# I2C_Peripherals.net
KiCad netlist of a schematic drawn in Altium Designer
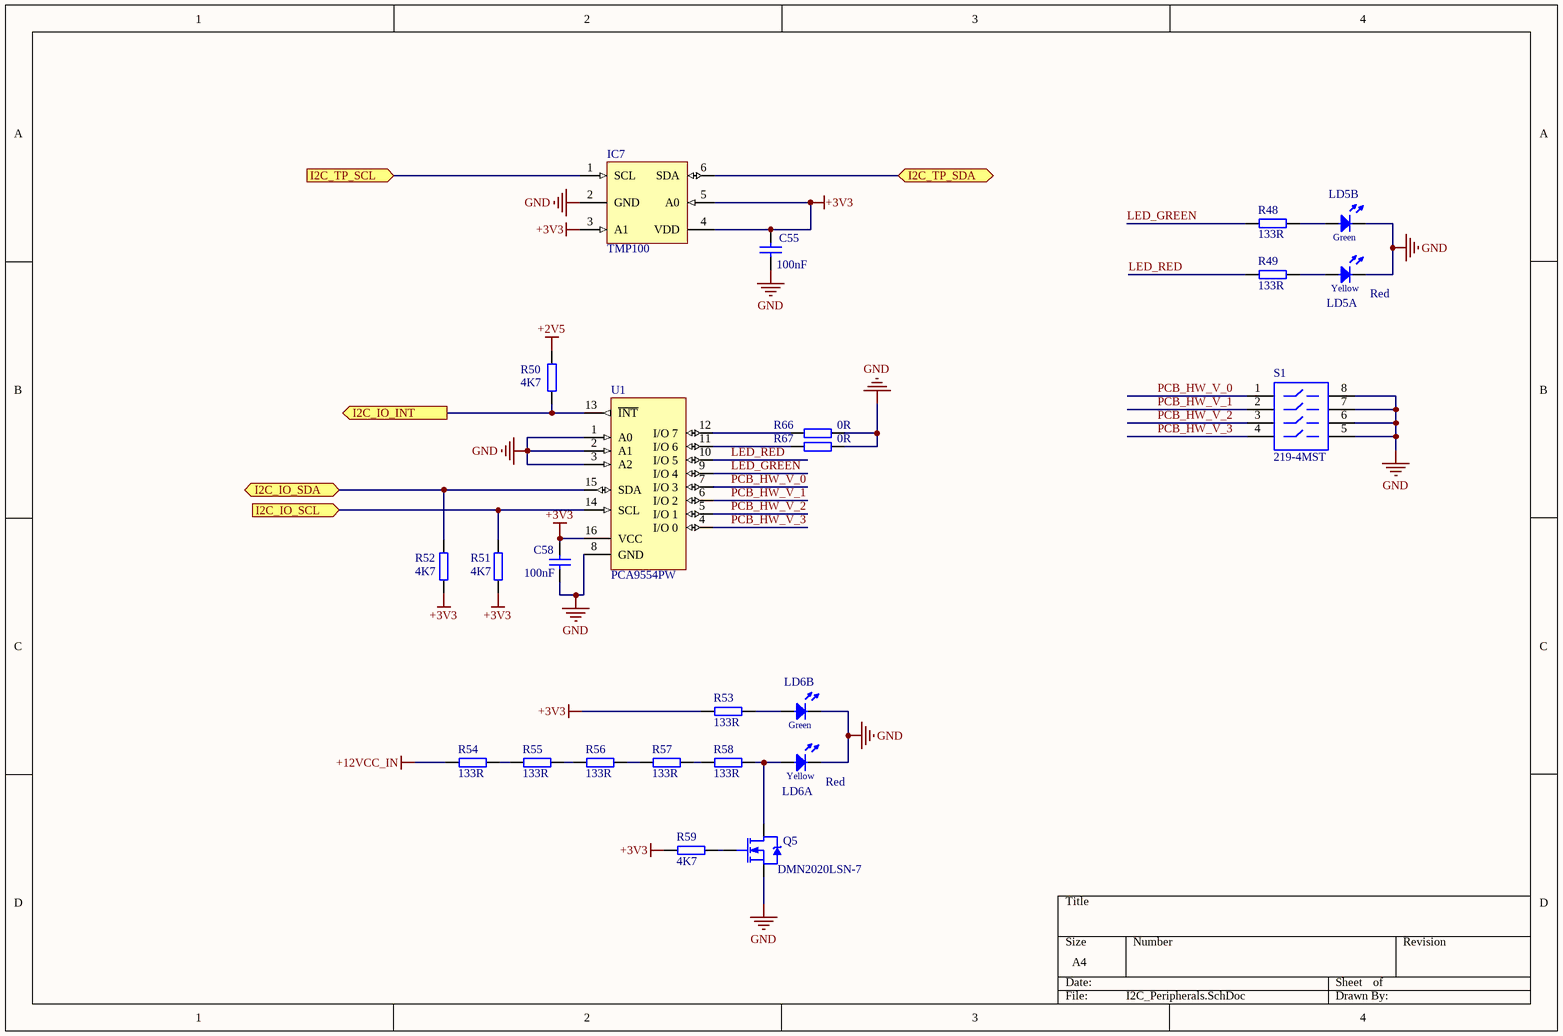
[diagram p0: I2C_Peripherals.SchDoc]

(export (version "E")
  (design (tool "Eeschema 10.0.6"))
  (components
    (comp (ref "C55")
      (value "100nF")
      (footprint "CC1608-0603")
      (description "Capacitor")
      (fields
        (field (name "TOLERANCE") "±10%")
        (field (name "VOLTAGE") "16V")
        (field (name "PUBLISHER") "Altium Limited")
      )
      (libsource (lib "wr_switch") (part "Cap"))
    )
    (comp (ref "C58")
      (value "100nF")
      (footprint "CC1608-0603")
      (description "Capacitor")
      (fields
        (field (name "TOLERANCE") "±10%")
        (field (name "VOLTAGE") "16V")
        (field (name "PUBLISHER") "Altium Limited")
      )
      (libsource (lib "wr_switch") (part "Cap"))
    )
    (comp (ref "IC7")
      (value "TMP100")
      (footprint "SOT23A-6L")
      (description "I2C temp. sensor")
      (libsource (lib "wr_switch") (part "TMP100"))
    )
    (comp (ref "LD5")
      (value "Red")
      (footprint "7S_WR:LED_DIALIGHT_591-3x0x-0xx")
      (description "Bi-Color LED SMD")
      (libsource (lib "wr_switch") (part "LED_DIALIGHT_591-3x0x"))
    )
    (comp (ref "LD6")
      (value "Red")
      (footprint "7S_WR:LED_DIALIGHT_591-3x0x-0xx")
      (description "Bi-Color LED SMD")
      (libsource (lib "wr_switch") (part "LED_DIALIGHT_591-3x0x"))
    )
    (comp (ref "Q5")
      (value "DMN2020LSN-7")
      (footprint "7S_WR:SC-59-3")
      (description "N-Channel Power MOSFET")
      (fields (field (name "MANUFACTURER") "Diodes Inc.") (field (name "PUBLISHER") "Altium Limited"))
      (libsource (lib "wr_switch") (part "NMOS-2"))
    )
    (comp (ref "R48")
      (value "133R")
      (footprint "0603")
      (description "SMD Resistor")
      (fields (field (name "TOLERANCE") "±1%"))
      (libsource (lib "wr_switch") (part "RES_SMD"))
    )
    (comp (ref "R49")
      (value "133R")
      (footprint "0603")
      (description "SMD Resistor")
      (fields (field (name "TOLERANCE") "±1%"))
      (libsource (lib "wr_switch") (part "RES_SMD"))
    )
    (comp (ref "R50")
      (value "4K7")
      (footprint "0603")
      (description "SMD Resistor")
      (fields (field (name "TOLERANCE") "±1%"))
      (libsource (lib "wr_switch") (part "RES_SMD"))
    )
    (comp (ref "R51")
      (value "4K7")
      (footprint "0603")
      (description "SMD Resistor")
      (fields (field (name "TOLERANCE") "±1%"))
      (libsource (lib "wr_switch") (part "RES_SMD"))
    )
    (comp (ref "R52")
      (value "4K7")
      (footprint "0603")
      (description "SMD Resistor")
      (fields (field (name "TOLERANCE") "±1%"))
      (libsource (lib "wr_switch") (part "RES_SMD"))
    )
    (comp (ref "R53")
      (value "133R")
      (footprint "0603")
      (description "SMD Resistor")
      (fields (field (name "TOLERANCE") "±1%"))
      (libsource (lib "wr_switch") (part "RES_SMD"))
    )
    (comp (ref "R54")
      (value "133R")
      (footprint "0603")
      (description "SMD Resistor")
      (fields (field (name "TOLERANCE") "±1%"))
      (libsource (lib "wr_switch") (part "RES_SMD"))
    )
    (comp (ref "R55")
      (value "133R")
      (footprint "0603")
      (description "SMD Resistor")
      (fields (field (name "TOLERANCE") "±1%"))
      (libsource (lib "wr_switch") (part "RES_SMD"))
    )
    (comp (ref "R56")
      (value "133R")
      (footprint "0603")
      (description "SMD Resistor")
      (fields (field (name "TOLERANCE") "±1%"))
      (libsource (lib "wr_switch") (part "RES_SMD"))
    )
    (comp (ref "R57")
      (value "133R")
      (footprint "0603")
      (description "SMD Resistor")
      (fields (field (name "TOLERANCE") "±1%"))
      (libsource (lib "wr_switch") (part "RES_SMD"))
    )
    (comp (ref "R58")
      (value "133R")
      (footprint "0603")
      (description "SMD Resistor")
      (fields (field (name "TOLERANCE") "±1%"))
      (libsource (lib "wr_switch") (part "RES_SMD"))
    )
    (comp (ref "R59")
      (value "4K7")
      (footprint "0603")
      (description "SMD Resistor")
      (fields (field (name "TOLERANCE") "±1%"))
      (libsource (lib "wr_switch") (part "RES_SMD"))
    )
    (comp (ref "R66")
      (value "0R")
      (footprint "0603")
      (description "SMD Resistor")
      (libsource (lib "wr_switch") (part "RES_SMD"))
    )
    (comp (ref "R67")
      (value "0R")
      (footprint "0603")
      (description "SMD Resistor")
      (libsource (lib "wr_switch") (part "RES_SMD"))
    )
    (comp (ref "S1")
      (value "219-4MST")
      (footprint "NHDS-8")
      (description "4 Positions DIP SWITCH")
      (libsource (lib "wr_switch") (part "SW-DIP4"))
    )
    (comp (ref "U1")
      (value "PCA9554PW")
      (footprint "SOP65P640X120-16N")
      (description "8-bit I2C-bus SMBus I/O port with interrupt")
      (libsource (lib "wr_switch") (part "PCA9554D"))
    )
  )
  (nets
    (net (code "1") (name "+2V5") (class "Default")
      (node (ref "R50") (pin "2") (pinfunction "2_2") (pintype "passive"))
    )
    (net (code "2") (name "+3V3") (class "Default")
      (node (ref "C55") (pin "2") (pinfunction "2_2") (pintype "passive"))
      (node (ref "C58") (pin "1") (pinfunction "1_1") (pintype "passive"))
      (node (ref "IC7") (pin "3") (pinfunction "A1_3") (pintype "input"))
      (node (ref "IC7") (pin "4") (pinfunction "VDD_4") (pintype "power_in"))
      (node (ref "IC7") (pin "5") (pinfunction "A0_5") (pintype "input"))
      (node (ref "R51") (pin "2") (pinfunction "2_2") (pintype "passive"))
      (node (ref "R52") (pin "2") (pinfunction "2_2") (pintype "passive"))
      (node (ref "R53") (pin "1") (pinfunction "1_1") (pintype "passive"))
      (node (ref "R59") (pin "2") (pinfunction "2_2") (pintype "passive"))
      (node (ref "U1") (pin "16") (pinfunction "VCC_16") (pintype "power_in"))
    )
    (net (code "3") (name "+12VCC_IN") (class "Default")
      (node (ref "R54") (pin "1") (pinfunction "1_1") (pintype "passive"))
    )
    (net (code "4") (name "/I2C_IO_INT") (class "Default")
      (node (ref "R50") (pin "1") (pinfunction "1_1") (pintype "passive"))
      (node (ref "U1") (pin "13") (pinfunction "~{INT}_13") (pintype "output"))
    )
    (net (code "5") (name "/I2C_IO_SCL") (class "Default")
      (node (ref "R51") (pin "1") (pinfunction "1_1") (pintype "passive"))
      (node (ref "U1") (pin "14") (pinfunction "SCL_14") (pintype "input"))
    )
    (net (code "6") (name "/I2C_IO_SDA") (class "Default")
      (node (ref "R52") (pin "1") (pinfunction "1_1") (pintype "passive"))
      (node (ref "U1") (pin "15") (pinfunction "SDA_15") (pintype "bidirectional"))
    )
    (net (code "7") (name "/I2C_TP_SCL") (class "Default")
      (node (ref "IC7") (pin "1") (pinfunction "SCL_1") (pintype "input"))
    )
    (net (code "8") (name "/I2C_TP_SDA") (class "Default")
      (node (ref "IC7") (pin "6") (pinfunction "SDA_6") (pintype "bidirectional"))
    )
    (net (code "9") (name "/LED_GREEN") (class "Default")
      (node (ref "R48") (pin "1") (pinfunction "1_1") (pintype "passive"))
      (node (ref "U1") (pin "9") (pinfunction "I/O_4_9") (pintype "bidirectional"))
    )
    (net (code "10") (name "/LED_RED") (class "Default")
      (node (ref "R49") (pin "1") (pinfunction "1_1") (pintype "passive"))
      (node (ref "U1") (pin "10") (pinfunction "I/O_5_10") (pintype "bidirectional"))
    )
    (net (code "11") (name "/PCB_HW_V_0") (class "Default")
      (node (ref "S1") (pin "1") (pinfunction "1_1") (pintype "passive"))
      (node (ref "U1") (pin "7") (pinfunction "I/O_3_7") (pintype "bidirectional"))
    )
    (net (code "12") (name "/PCB_HW_V_1") (class "Default")
      (node (ref "S1") (pin "2") (pinfunction "2_2") (pintype "passive"))
      (node (ref "U1") (pin "6") (pinfunction "I/O_2_6") (pintype "bidirectional"))
    )
    (net (code "13") (name "/PCB_HW_V_2") (class "Default")
      (node (ref "S1") (pin "3") (pinfunction "3_3") (pintype "passive"))
      (node (ref "U1") (pin "5") (pinfunction "I/O_1_5") (pintype "bidirectional"))
    )
    (net (code "14") (name "/PCB_HW_V_3") (class "Default")
      (node (ref "S1") (pin "4") (pinfunction "4_4") (pintype "passive"))
      (node (ref "U1") (pin "4") (pinfunction "I/O_0_4") (pintype "bidirectional"))
    )
    (net (code "15") (name "GND") (class "Default")
      (node (ref "C55") (pin "1") (pinfunction "1_1") (pintype "passive"))
      (node (ref "C58") (pin "2") (pinfunction "2_2") (pintype "passive"))
      (node (ref "IC7") (pin "2") (pinfunction "GND_2") (pintype "power_in"))
      (node (ref "LD5") (pin "1") (pinfunction "C_1") (pintype "passive"))
      (node (ref "LD5") (pin "4") (pinfunction "C_4") (pintype "passive"))
      (node (ref "LD6") (pin "1") (pinfunction "C_1") (pintype "passive"))
      (node (ref "LD6") (pin "4") (pinfunction "C_4") (pintype "passive"))
      (node (ref "Q5") (pin "3") (pinfunction "S_3") (pintype "passive"))
      (node (ref "R66") (pin "2") (pinfunction "2_2") (pintype "passive"))
      (node (ref "R67") (pin "2") (pinfunction "2_2") (pintype "passive"))
      (node (ref "S1") (pin "5") (pinfunction "5_5") (pintype "passive"))
      (node (ref "S1") (pin "6") (pinfunction "6_6") (pintype "passive"))
      (node (ref "S1") (pin "7") (pinfunction "7_7") (pintype "passive"))
      (node (ref "S1") (pin "8") (pinfunction "8_8") (pintype "passive"))
      (node (ref "U1") (pin "1") (pinfunction "A0_1") (pintype "input"))
      (node (ref "U1") (pin "2") (pinfunction "A1_2") (pintype "input"))
      (node (ref "U1") (pin "3") (pinfunction "A2_3") (pintype "input"))
      (node (ref "U1") (pin "8") (pinfunction "GND_8") (pintype "power_in"))
    )
    (net (code "16") (name "Net-(LD5A-A)") (class "Default")
      (node (ref "LD5") (pin "2") (pinfunction "A_2") (pintype "passive"))
      (node (ref "R49") (pin "2") (pinfunction "2_2") (pintype "passive"))
    )
    (net (code "17") (name "Net-(LD5B-A)") (class "Default")
      (node (ref "LD5") (pin "3") (pinfunction "A_3") (pintype "passive"))
      (node (ref "R48") (pin "2") (pinfunction "2_2") (pintype "passive"))
    )
    (net (code "18") (name "Net-(LD6A-A)") (class "Default")
      (node (ref "LD6") (pin "2") (pinfunction "A_2") (pintype "passive"))
      (node (ref "Q5") (pin "2") (pinfunction "D_2") (pintype "passive"))
      (node (ref "R58") (pin "2") (pinfunction "2_2") (pintype "passive"))
    )
    (net (code "19") (name "Net-(LD6B-A)") (class "Default")
      (node (ref "LD6") (pin "3") (pinfunction "A_3") (pintype "passive"))
      (node (ref "R53") (pin "2") (pinfunction "2_2") (pintype "passive"))
    )
    (net (code "20") (name "Net-(Q5-G)") (class "Default")
      (node (ref "Q5") (pin "1") (pinfunction "G_1") (pintype "passive"))
      (node (ref "R59") (pin "1") (pinfunction "1_1") (pintype "passive"))
    )
    (net (code "21") (name "Net-(R54-Pad2)") (class "Default")
      (node (ref "R54") (pin "2") (pinfunction "2_2") (pintype "passive"))
      (node (ref "R55") (pin "1") (pinfunction "1_1") (pintype "passive"))
    )
    (net (code "22") (name "Net-(R55-Pad2)") (class "Default")
      (node (ref "R55") (pin "2") (pinfunction "2_2") (pintype "passive"))
      (node (ref "R56") (pin "1") (pinfunction "1_1") (pintype "passive"))
    )
    (net (code "23") (name "Net-(R56-Pad2)") (class "Default")
      (node (ref "R56") (pin "2") (pinfunction "2_2") (pintype "passive"))
      (node (ref "R57") (pin "1") (pinfunction "1_1") (pintype "passive"))
    )
    (net (code "24") (name "Net-(R57-Pad2)") (class "Default")
      (node (ref "R57") (pin "2") (pinfunction "2_2") (pintype "passive"))
      (node (ref "R58") (pin "1") (pinfunction "1_1") (pintype "passive"))
    )
    (net (code "25") (name "Net-(U1-I{slash}O_6)") (class "Default")
      (node (ref "R67") (pin "1") (pinfunction "1_1") (pintype "passive"))
      (node (ref "U1") (pin "11") (pinfunction "I/O_6_11") (pintype "bidirectional"))
    )
    (net (code "26") (name "Net-(U1-I{slash}O_7)") (class "Default")
      (node (ref "R66") (pin "1") (pinfunction "1_1") (pintype "passive"))
      (node (ref "U1") (pin "12") (pinfunction "I/O_7_12") (pintype "bidirectional"))
    )
  )
)
